# Input_protect.net
KiCad netlist of a schematic drawn in Altium Designer
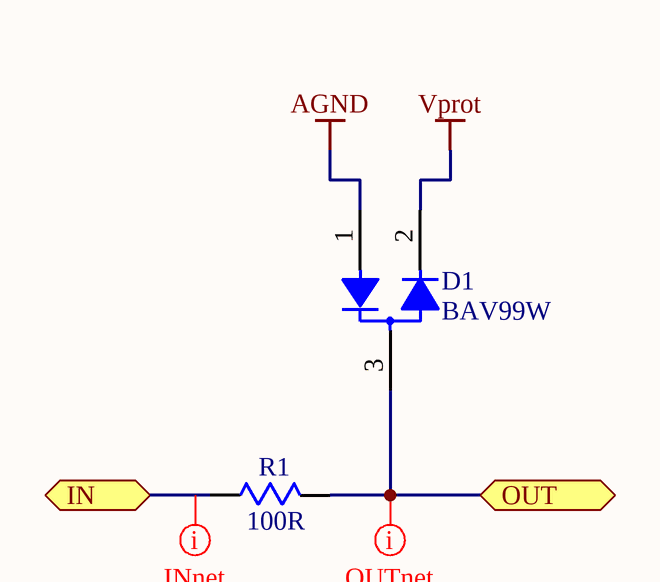
[diagram p0: Input protect.SchDoc]

(export (version "E")
  (design (tool "Eeschema 10.0.6"))
  (components
    (comp (ref "D1") (value "BAV99W") (footprint "SMD/SOT323") (libsource (lib "My_lib") (part "BAV99")))
    (comp (ref "R1") (value "100R") (footprint "SMD/R/0805") (libsource (lib "My_lib") (part "Resistor")))
  )
  (nets
    (net (code "1") (name "/IN") (class "Default")
      (node (ref "R1") (pin "1") (pinfunction "1_1") (pintype "passive"))
    )
    (net (code "2") (name "/OUT") (class "Default")
      (node (ref "D1") (pin "3") (pinfunction "3_3") (pintype "passive"))
      (node (ref "R1") (pin "2") (pinfunction "2_2") (pintype "passive"))
    )
    (net (code "3") (name "AGND") (class "Default")
      (node (ref "D1") (pin "1") (pinfunction "1_1") (pintype "passive"))
    )
    (net (code "4") (name "Vprot") (class "Default")
      (node (ref "D1") (pin "2") (pinfunction "2_2") (pintype "passive"))
    )
  )
)
